# time_circuits1_3.net
KiCad netlist of a schematic drawn in EAGLE
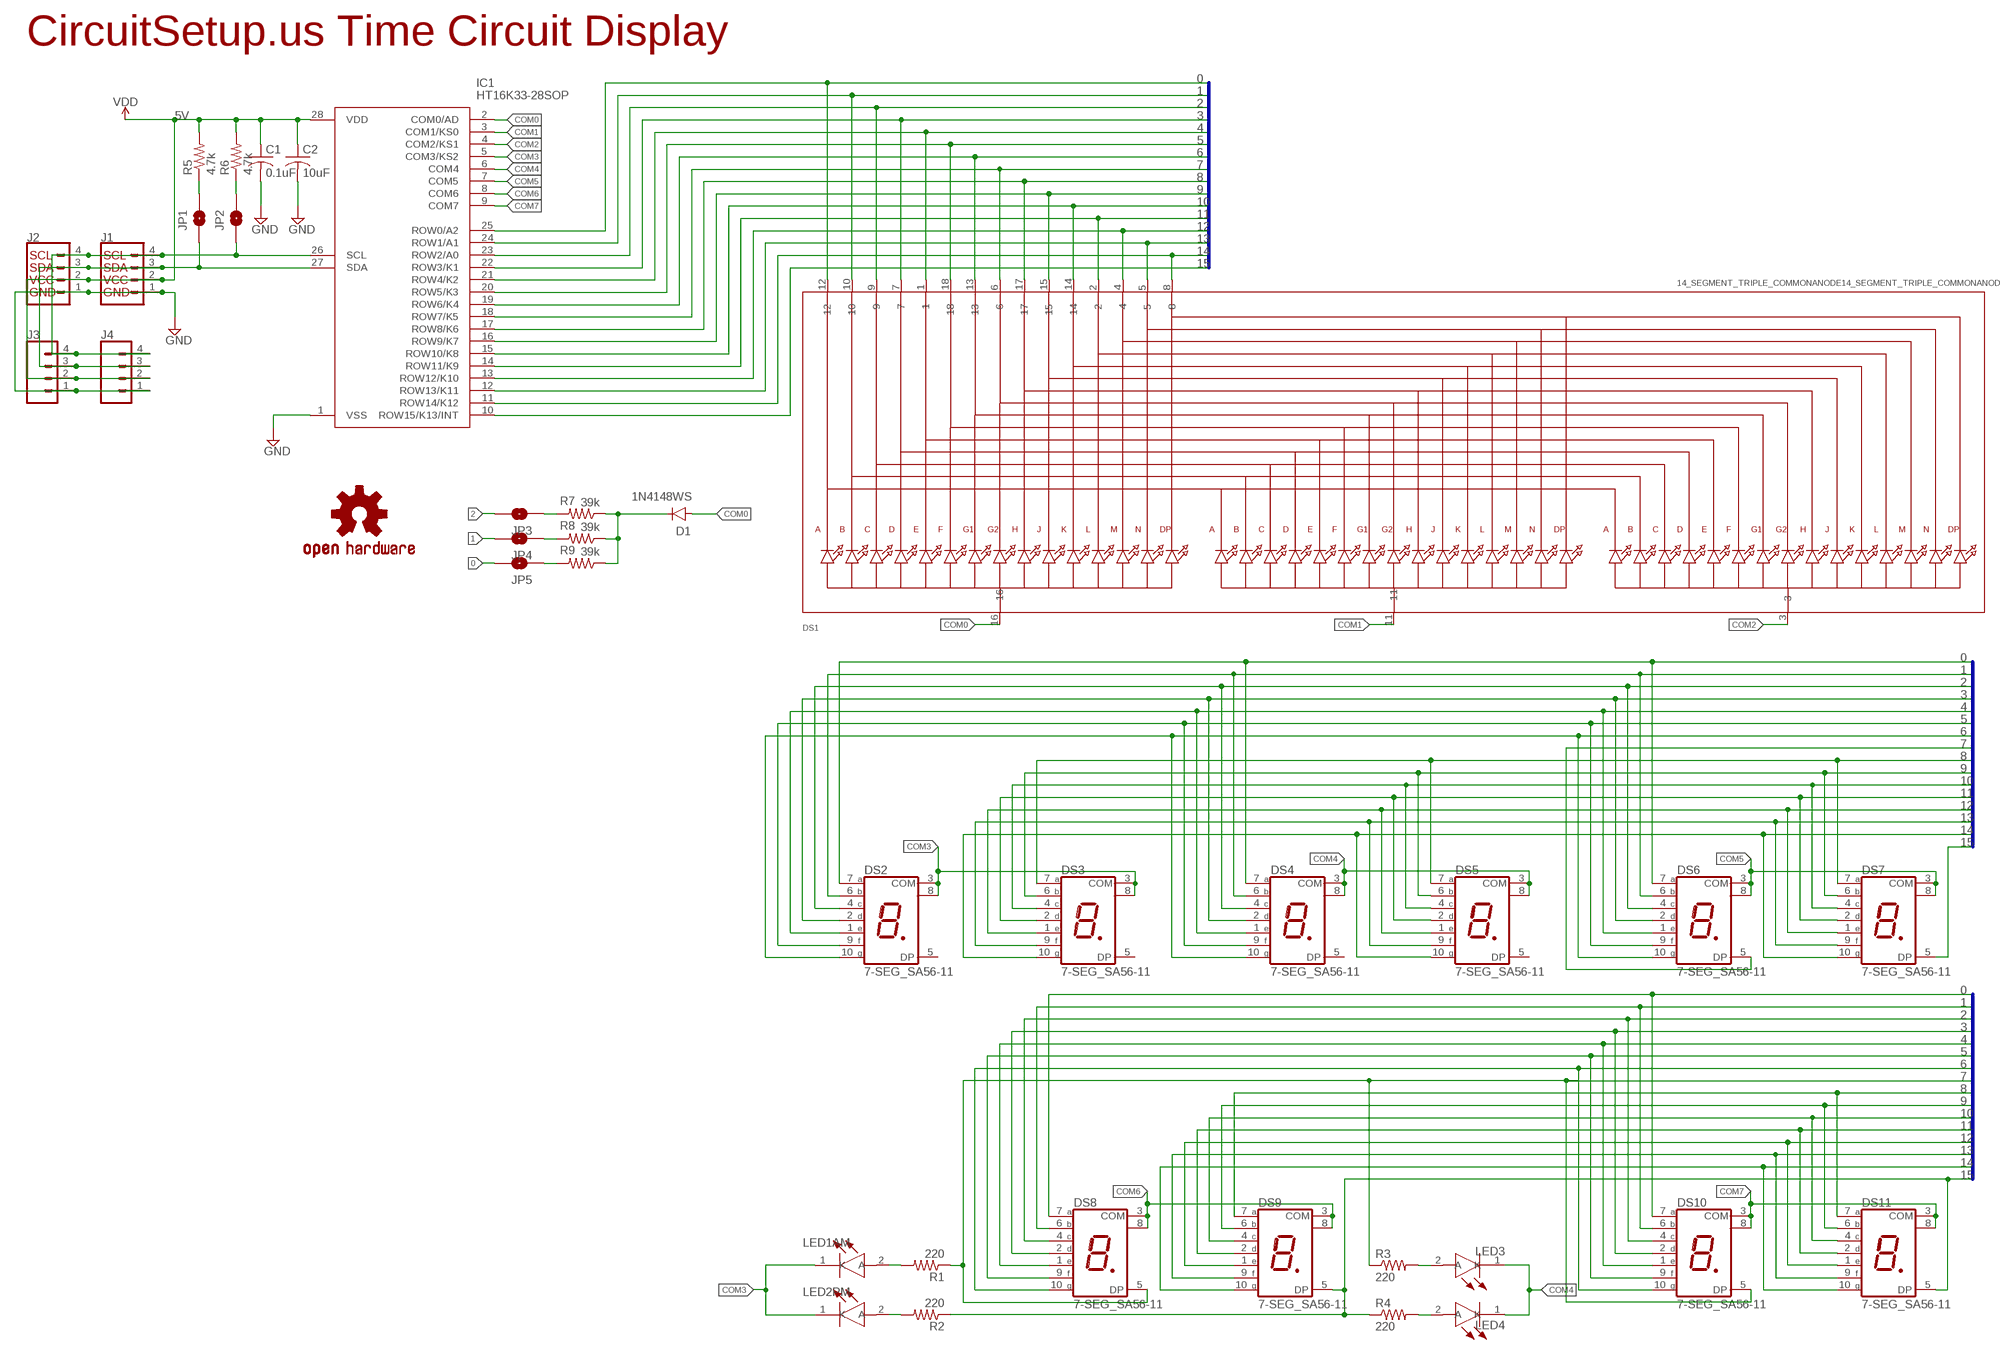
[diagram p0: schematic, sheet 1]

(export (version "E")
  (design (tool "Eeschema 10.0.6"))
  (components
    (comp (ref "C1")
      (value "0.1uF")
      (footprint "eagle-import:C0603")
      (libsource (lib "eagle-import") (part "C-USC0603"))
    )
    (comp (ref "C2")
      (value "10uF")
      (footprint "eagle-import:C0603")
      (libsource (lib "eagle-import") (part "C-USC0603"))
    )
    (comp (ref "D1")
      (value "1N4148WS")
      (footprint "eagle-import:SOD-323")
      (fields
        (field (name "DIGIKEY_PART_NUMBER") "1N4148WSFSTR-ND")
        (field (name "MANUFACTURER") "Diodes Incorporated")
        (field (name "CREATED_BY") "PCBLayout.com")
      )
      (libsource (lib "eagle-import") (part "1N4148WS"))
    )
    (comp (ref "DS1")
      (value "14_SEGMENT_TRIPLE_COMMONANODE14_SEGMENT_TRIPLE_COMMONANODE")
      (footprint "eagle-import:SEGMENT_TRIPLE_14")
      (libsource (lib "eagle-import") (part "14_SEGMENT_TRIPLE_COMMONANODE14_SEGMENT_TRIPLE_COMMONANODE"))
    )
    (comp (ref "DS2")
      (value "7-SEG_SA56-11")
      (footprint "eagle-import:SA56-11")
      (libsource (lib "eagle-import") (part "7-SEG_SA56-11"))
    )
    (comp (ref "DS3")
      (value "7-SEG_SA56-11")
      (footprint "eagle-import:SA56-11")
      (libsource (lib "eagle-import") (part "7-SEG_SA56-11"))
    )
    (comp (ref "DS4")
      (value "7-SEG_SA56-11")
      (footprint "eagle-import:SA56-11")
      (libsource (lib "eagle-import") (part "7-SEG_SA56-11"))
    )
    (comp (ref "DS5")
      (value "7-SEG_SA56-11")
      (footprint "eagle-import:SA56-11")
      (libsource (lib "eagle-import") (part "7-SEG_SA56-11"))
    )
    (comp (ref "DS6")
      (value "7-SEG_SA56-11")
      (footprint "eagle-import:SA56-11")
      (libsource (lib "eagle-import") (part "7-SEG_SA56-11"))
    )
    (comp (ref "DS7")
      (value "7-SEG_SA56-11")
      (footprint "eagle-import:SA56-11")
      (libsource (lib "eagle-import") (part "7-SEG_SA56-11"))
    )
    (comp (ref "DS8")
      (value "7-SEG_SA56-11")
      (footprint "eagle-import:SA56-11")
      (libsource (lib "eagle-import") (part "7-SEG_SA56-11"))
    )
    (comp (ref "DS9")
      (value "7-SEG_SA56-11")
      (footprint "eagle-import:SA56-11")
      (libsource (lib "eagle-import") (part "7-SEG_SA56-11"))
    )
    (comp (ref "DS10")
      (value "7-SEG_SA56-11")
      (footprint "eagle-import:SA56-11")
      (libsource (lib "eagle-import") (part "7-SEG_SA56-11"))
    )
    (comp (ref "DS11")
      (value "7-SEG_SA56-11")
      (footprint "eagle-import:SA56-11")
      (libsource (lib "eagle-import") (part "7-SEG_SA56-11"))
    )
    (comp (ref "IC1")
      (value "HT16K33-28SOP")
      (footprint "eagle-import:SOIC127P1031X264-28N")
      (libsource (lib "eagle-import") (part "HT16K33-28SOP"))
    )
    (comp (ref "J1")
      (value "I2C_STANDARD")
      (footprint "eagle-import:1X04")
      (libsource (lib "eagle-import") (part "I2C_STANDARD"))
    )
    (comp (ref "J2")
      (value "I2C_STANDARD")
      (footprint "eagle-import:1X04")
      (libsource (lib "eagle-import") (part "I2C_STANDARD"))
    )
    (comp (ref "J3")
      (value "CONN_04SMD_2.54")
      (footprint "eagle-import:1X04_5.5MM_STRAIGHT")
      (libsource (lib "eagle-import") (part "CONN_04SMD_2.54"))
    )
    (comp (ref "J4")
      (value "CONN_04SMD_2.54")
      (footprint "eagle-import:1X04_5.5MM_STRAIGHT")
      (libsource (lib "eagle-import") (part "CONN_04SMD_2.54"))
    )
    (comp (ref "JP1")
      (value "JUMPER-SMT_2_NO_SILK")
      (footprint "eagle-import:SMT-JUMPER_2_NO_SILK")
      (libsource (lib "eagle-import") (part "JUMPER-SMT_2_NO_SILK"))
    )
    (comp (ref "JP2")
      (value "JUMPER-SMT_2_NO_SILK")
      (footprint "eagle-import:SMT-JUMPER_2_NO_SILK")
      (libsource (lib "eagle-import") (part "JUMPER-SMT_2_NO_SILK"))
    )
    (comp (ref "JP3")
      (value "JUMPER-SMT_2_NO_SILK")
      (footprint "eagle-import:SMT-JUMPER_2_NO_SILK")
      (libsource (lib "eagle-import") (part "JUMPER-SMT_2_NO_SILK"))
    )
    (comp (ref "JP4")
      (value "JUMPER-SMT_2_NO_SILK")
      (footprint "eagle-import:SMT-JUMPER_2_NO_SILK")
      (libsource (lib "eagle-import") (part "JUMPER-SMT_2_NO_SILK"))
    )
    (comp (ref "JP5")
      (value "JUMPER-SMT_2_NO_SILK")
      (footprint "eagle-import:SMT-JUMPER_2_NO_SILK")
      (libsource (lib "eagle-import") (part "JUMPER-SMT_2_NO_SILK"))
    )
    (comp (ref "LED1AM")
      (value "WP132XGD")
      (footprint "eagle-import:WP132XGD")
      (fields (field (name "MOUSER_PART_NUMBER") "604-WP132XGD"))
      (libsource (lib "eagle-import") (part "WP132XGD"))
    )
    (comp (ref "LED2PM")
      (value "WP132XGD")
      (footprint "eagle-import:WP132XGD")
      (fields (field (name "MOUSER_PART_NUMBER") "604-WP132XGD"))
      (libsource (lib "eagle-import") (part "WP132XGD"))
    )
    (comp (ref "LED3")
      (value "WP132XGD")
      (footprint "eagle-import:WP132XGD")
      (fields (field (name "MOUSER_PART_NUMBER") "604-WP132XGD"))
      (libsource (lib "eagle-import") (part "WP132XGD"))
    )
    (comp (ref "LED4")
      (value "WP132XGD")
      (footprint "eagle-import:WP132XGD")
      (fields (field (name "MOUSER_PART_NUMBER") "604-WP132XGD"))
      (libsource (lib "eagle-import") (part "WP132XGD"))
    )
    (comp (ref "LOGO1")
      (value "OSHW-LOGOL")
      (footprint "eagle-import:OSHW-LOGO-L")
      (libsource (lib "eagle-import") (part "OSHW-LOGOL"))
    )
    (comp (ref "R1")
      (value "220")
      (footprint "eagle-import:R0603")
      (libsource (lib "eagle-import") (part "R-US_R0603"))
    )
    (comp (ref "R2")
      (value "220")
      (footprint "eagle-import:R0603")
      (libsource (lib "eagle-import") (part "R-US_R0603"))
    )
    (comp (ref "R3")
      (value "220")
      (footprint "eagle-import:R0603")
      (libsource (lib "eagle-import") (part "R-US_R0603"))
    )
    (comp (ref "R4")
      (value "220")
      (footprint "eagle-import:R0603")
      (libsource (lib "eagle-import") (part "R-US_R0603"))
    )
    (comp (ref "R5")
      (value "4.7k")
      (footprint "eagle-import:R0603")
      (libsource (lib "eagle-import") (part "R-US_R0603"))
    )
    (comp (ref "R6")
      (value "4.7k")
      (footprint "eagle-import:R0603")
      (libsource (lib "eagle-import") (part "R-US_R0603"))
    )
    (comp (ref "R7")
      (value "39k")
      (footprint "eagle-import:R0603")
      (libsource (lib "eagle-import") (part "R-US_R0603"))
    )
    (comp (ref "R8")
      (value "39k")
      (footprint "eagle-import:R0603")
      (libsource (lib "eagle-import") (part "R-US_R0603"))
    )
    (comp (ref "R9")
      (value "39k")
      (footprint "eagle-import:R0603")
      (libsource (lib "eagle-import") (part "R-US_R0603"))
    )
  )
  (nets
    (net (code "1") (name "/3") (class "Default")
      (node (ref "DS1") (pin "7") (pinfunction "7_7") (pintype "bidirectional"))
      (node (ref "DS10") (pin "2") (pinfunction "D_2") (pintype "passive"))
      (node (ref "DS2") (pin "2") (pinfunction "D_2") (pintype "passive"))
      (node (ref "DS4") (pin "2") (pinfunction "D_2") (pintype "passive"))
      (node (ref "DS6") (pin "2") (pinfunction "D_2") (pintype "passive"))
      (node (ref "DS8") (pin "2") (pinfunction "D_2") (pintype "passive"))
      (node (ref "IC1") (pin "22") (pinfunction "ROW3/K1_22") (pintype "bidirectional"))
    )
    (net (code "2") (name "/4") (class "Default")
      (node (ref "DS1") (pin "1") (pinfunction "1_1") (pintype "bidirectional"))
      (node (ref "DS10") (pin "1") (pinfunction "E_1") (pintype "passive"))
      (node (ref "DS2") (pin "1") (pinfunction "E_1") (pintype "passive"))
      (node (ref "DS4") (pin "1") (pinfunction "E_1") (pintype "passive"))
      (node (ref "DS6") (pin "1") (pinfunction "E_1") (pintype "passive"))
      (node (ref "DS8") (pin "1") (pinfunction "E_1") (pintype "passive"))
      (node (ref "IC1") (pin "21") (pinfunction "ROW4/K2_21") (pintype "bidirectional"))
    )
    (net (code "3") (name "/5") (class "Default")
      (node (ref "DS1") (pin "18") (pinfunction "18_18") (pintype "bidirectional"))
      (node (ref "DS10") (pin "9") (pinfunction "F_9") (pintype "passive"))
      (node (ref "DS2") (pin "9") (pinfunction "F_9") (pintype "passive"))
      (node (ref "DS4") (pin "9") (pinfunction "F_9") (pintype "passive"))
      (node (ref "DS6") (pin "9") (pinfunction "F_9") (pintype "passive"))
      (node (ref "DS8") (pin "9") (pinfunction "F_9") (pintype "passive"))
      (node (ref "IC1") (pin "20") (pinfunction "ROW5/K3_20") (pintype "bidirectional"))
    )
    (net (code "4") (name "/6") (class "Default")
      (node (ref "DS1") (pin "13") (pinfunction "13_13") (pintype "bidirectional"))
      (node (ref "DS10") (pin "10") (pinfunction "G_10") (pintype "passive"))
      (node (ref "DS2") (pin "10") (pinfunction "G_10") (pintype "passive"))
      (node (ref "DS4") (pin "10") (pinfunction "G_10") (pintype "passive"))
      (node (ref "DS6") (pin "10") (pinfunction "G_10") (pintype "passive"))
      (node (ref "DS8") (pin "10") (pinfunction "G_10") (pintype "passive"))
      (node (ref "IC1") (pin "19") (pinfunction "ROW6/K4_19") (pintype "bidirectional"))
    )
    (net (code "5") (name "/7") (class "Default")
      (node (ref "DS1") (pin "6") (pinfunction "6_6") (pintype "bidirectional"))
      (node (ref "DS10") (pin "5") (pinfunction "DP_5") (pintype "passive"))
      (node (ref "DS6") (pin "5") (pinfunction "DP_5") (pintype "passive"))
      (node (ref "DS8") (pin "5") (pinfunction "DP_5") (pintype "passive"))
      (node (ref "IC1") (pin "18") (pinfunction "ROW7/K5_18") (pintype "bidirectional"))
      (node (ref "R1") (pin "1") (pinfunction "1_1") (pintype "passive"))
      (node (ref "R3") (pin "1") (pinfunction "1_1") (pintype "passive"))
    )
    (net (code "6") (name "/8") (class "Default")
      (node (ref "DS1") (pin "17") (pinfunction "17_17") (pintype "bidirectional"))
      (node (ref "DS11") (pin "7") (pinfunction "A_7") (pintype "passive"))
      (node (ref "DS3") (pin "7") (pinfunction "A_7") (pintype "passive"))
      (node (ref "DS5") (pin "7") (pinfunction "A_7") (pintype "passive"))
      (node (ref "DS7") (pin "7") (pinfunction "A_7") (pintype "passive"))
      (node (ref "DS9") (pin "7") (pinfunction "A_7") (pintype "passive"))
      (node (ref "IC1") (pin "17") (pinfunction "ROW8/K6_17") (pintype "bidirectional"))
    )
    (net (code "7") (name "/9") (class "Default")
      (node (ref "DS1") (pin "15") (pinfunction "15_15") (pintype "bidirectional"))
      (node (ref "DS11") (pin "6") (pinfunction "B_6") (pintype "passive"))
      (node (ref "DS3") (pin "6") (pinfunction "B_6") (pintype "passive"))
      (node (ref "DS5") (pin "6") (pinfunction "B_6") (pintype "passive"))
      (node (ref "DS7") (pin "6") (pinfunction "B_6") (pintype "passive"))
      (node (ref "DS9") (pin "6") (pinfunction "B_6") (pintype "passive"))
      (node (ref "IC1") (pin "16") (pinfunction "ROW9/K7_16") (pintype "bidirectional"))
    )
    (net (code "8") (name "/10") (class "Default")
      (node (ref "DS1") (pin "14") (pinfunction "14_14") (pintype "bidirectional"))
      (node (ref "DS11") (pin "4") (pinfunction "C_4") (pintype "passive"))
      (node (ref "DS3") (pin "4") (pinfunction "C_4") (pintype "passive"))
      (node (ref "DS5") (pin "4") (pinfunction "C_4") (pintype "passive"))
      (node (ref "DS7") (pin "4") (pinfunction "C_4") (pintype "passive"))
      (node (ref "DS9") (pin "4") (pinfunction "C_4") (pintype "passive"))
      (node (ref "IC1") (pin "15") (pinfunction "ROW10/K8_15") (pintype "bidirectional"))
    )
    (net (code "9") (name "/11") (class "Default")
      (node (ref "DS1") (pin "2") (pinfunction "2_2") (pintype "bidirectional"))
      (node (ref "DS11") (pin "2") (pinfunction "D_2") (pintype "passive"))
      (node (ref "DS3") (pin "2") (pinfunction "D_2") (pintype "passive"))
      (node (ref "DS5") (pin "2") (pinfunction "D_2") (pintype "passive"))
      (node (ref "DS7") (pin "2") (pinfunction "D_2") (pintype "passive"))
      (node (ref "DS9") (pin "2") (pinfunction "D_2") (pintype "passive"))
      (node (ref "IC1") (pin "14") (pinfunction "ROW11/K9_14") (pintype "bidirectional"))
    )
    (net (code "10") (name "/12") (class "Default")
      (node (ref "DS1") (pin "4") (pinfunction "4_4") (pintype "bidirectional"))
      (node (ref "DS11") (pin "1") (pinfunction "E_1") (pintype "passive"))
      (node (ref "DS3") (pin "1") (pinfunction "E_1") (pintype "passive"))
      (node (ref "DS5") (pin "1") (pinfunction "E_1") (pintype "passive"))
      (node (ref "DS7") (pin "1") (pinfunction "E_1") (pintype "passive"))
      (node (ref "DS9") (pin "1") (pinfunction "E_1") (pintype "passive"))
      (node (ref "IC1") (pin "13") (pinfunction "ROW12/K10_13") (pintype "bidirectional"))
    )
    (net (code "11") (name "/13") (class "Default")
      (node (ref "DS1") (pin "5") (pinfunction "5_5") (pintype "bidirectional"))
      (node (ref "DS11") (pin "9") (pinfunction "F_9") (pintype "passive"))
      (node (ref "DS3") (pin "9") (pinfunction "F_9") (pintype "passive"))
      (node (ref "DS5") (pin "9") (pinfunction "F_9") (pintype "passive"))
      (node (ref "DS7") (pin "9") (pinfunction "F_9") (pintype "passive"))
      (node (ref "DS9") (pin "9") (pinfunction "F_9") (pintype "passive"))
      (node (ref "IC1") (pin "12") (pinfunction "ROW13/K11_12") (pintype "bidirectional"))
    )
    (net (code "12") (name "/14") (class "Default")
      (node (ref "DS1") (pin "8") (pinfunction "8_8") (pintype "bidirectional"))
      (node (ref "DS11") (pin "10") (pinfunction "G_10") (pintype "passive"))
      (node (ref "DS3") (pin "10") (pinfunction "G_10") (pintype "passive"))
      (node (ref "DS5") (pin "10") (pinfunction "G_10") (pintype "passive"))
      (node (ref "DS7") (pin "10") (pinfunction "G_10") (pintype "passive"))
      (node (ref "DS9") (pin "10") (pinfunction "G_10") (pintype "passive"))
      (node (ref "IC1") (pin "11") (pinfunction "ROW14/K12_11") (pintype "bidirectional"))
    )
    (net (code "13") (name "/15") (class "Default")
      (node (ref "DS11") (pin "5") (pinfunction "DP_5") (pintype "passive"))
      (node (ref "DS7") (pin "5") (pinfunction "DP_5") (pintype "passive"))
      (node (ref "DS9") (pin "5") (pinfunction "DP_5") (pintype "passive"))
      (node (ref "IC1") (pin "10") (pinfunction "ROW15/K13/INT_10") (pintype "bidirectional"))
      (node (ref "R2") (pin "1") (pinfunction "1_1") (pintype "passive"))
      (node (ref "R4") (pin "1") (pinfunction "1_1") (pintype "passive"))
    )
    (net (code "14") (name "0") (class "Default")
      (node (ref "DS1") (pin "12") (pinfunction "12_12") (pintype "bidirectional"))
      (node (ref "DS10") (pin "7") (pinfunction "A_7") (pintype "passive"))
      (node (ref "DS2") (pin "7") (pinfunction "A_7") (pintype "passive"))
      (node (ref "DS4") (pin "7") (pinfunction "A_7") (pintype "passive"))
      (node (ref "DS6") (pin "7") (pinfunction "A_7") (pintype "passive"))
      (node (ref "DS8") (pin "7") (pinfunction "A_7") (pintype "passive"))
      (node (ref "IC1") (pin "25") (pinfunction "ROW0/A2_25") (pintype "bidirectional"))
      (node (ref "JP5") (pin "2") (pinfunction "2_2") (pintype "passive"))
    )
    (net (code "15") (name "1") (class "Default")
      (node (ref "DS1") (pin "10") (pinfunction "10_10") (pintype "bidirectional"))
      (node (ref "DS10") (pin "6") (pinfunction "B_6") (pintype "passive"))
      (node (ref "DS2") (pin "6") (pinfunction "B_6") (pintype "passive"))
      (node (ref "DS4") (pin "6") (pinfunction "B_6") (pintype "passive"))
      (node (ref "DS6") (pin "6") (pinfunction "B_6") (pintype "passive"))
      (node (ref "DS8") (pin "6") (pinfunction "B_6") (pintype "passive"))
      (node (ref "IC1") (pin "24") (pinfunction "ROW1/A1_24") (pintype "bidirectional"))
      (node (ref "JP4") (pin "2") (pinfunction "2_2") (pintype "passive"))
    )
    (net (code "16") (name "2") (class "Default")
      (node (ref "DS1") (pin "9") (pinfunction "9_9") (pintype "bidirectional"))
      (node (ref "DS10") (pin "4") (pinfunction "C_4") (pintype "passive"))
      (node (ref "DS2") (pin "4") (pinfunction "C_4") (pintype "passive"))
      (node (ref "DS4") (pin "4") (pinfunction "C_4") (pintype "passive"))
      (node (ref "DS6") (pin "4") (pinfunction "C_4") (pintype "passive"))
      (node (ref "DS8") (pin "4") (pinfunction "C_4") (pintype "passive"))
      (node (ref "IC1") (pin "23") (pinfunction "ROW2/A0_23") (pintype "bidirectional"))
      (node (ref "JP3") (pin "2") (pinfunction "2_2") (pintype "passive"))
    )
    (net (code "17") (name "COM0") (class "Default")
      (node (ref "D1") (pin "A") (pinfunction "A_A") (pintype "passive"))
      (node (ref "DS1") (pin "16") (pinfunction "16_16") (pintype "bidirectional"))
      (node (ref "IC1") (pin "2") (pinfunction "COM0/AD_2") (pintype "bidirectional"))
    )
    (net (code "18") (name "COM1") (class "Default")
      (node (ref "DS1") (pin "11") (pinfunction "11_11") (pintype "bidirectional"))
      (node (ref "IC1") (pin "3") (pinfunction "COM1/KS0_3") (pintype "bidirectional"))
    )
    (net (code "19") (name "COM2") (class "Default")
      (node (ref "DS1") (pin "3") (pinfunction "3_3") (pintype "bidirectional"))
      (node (ref "IC1") (pin "4") (pinfunction "COM2/KS1_4") (pintype "bidirectional"))
    )
    (net (code "20") (name "COM3") (class "Default")
      (node (ref "DS2") (pin "3") (pinfunction "COM_3") (pintype "passive"))
      (node (ref "DS2") (pin "8") (pinfunction "COM_8") (pintype "passive"))
      (node (ref "DS3") (pin "3") (pinfunction "COM_3") (pintype "passive"))
      (node (ref "DS3") (pin "8") (pinfunction "COM_8") (pintype "passive"))
      (node (ref "IC1") (pin "5") (pinfunction "COM3/KS2_5") (pintype "bidirectional"))
      (node (ref "LED1AM") (pin "1") (pinfunction "K_1") (pintype "bidirectional"))
      (node (ref "LED2PM") (pin "1") (pinfunction "K_1") (pintype "bidirectional"))
    )
    (net (code "21") (name "COM4") (class "Default")
      (node (ref "DS4") (pin "3") (pinfunction "COM_3") (pintype "passive"))
      (node (ref "DS4") (pin "8") (pinfunction "COM_8") (pintype "passive"))
      (node (ref "DS5") (pin "3") (pinfunction "COM_3") (pintype "passive"))
      (node (ref "DS5") (pin "8") (pinfunction "COM_8") (pintype "passive"))
      (node (ref "IC1") (pin "6") (pinfunction "COM4_6") (pintype "bidirectional"))
      (node (ref "LED3") (pin "1") (pinfunction "K_1") (pintype "bidirectional"))
      (node (ref "LED4") (pin "1") (pinfunction "K_1") (pintype "bidirectional"))
    )
    (net (code "22") (name "COM5") (class "Default")
      (node (ref "DS6") (pin "3") (pinfunction "COM_3") (pintype "passive"))
      (node (ref "DS6") (pin "8") (pinfunction "COM_8") (pintype "passive"))
      (node (ref "DS7") (pin "3") (pinfunction "COM_3") (pintype "passive"))
      (node (ref "DS7") (pin "8") (pinfunction "COM_8") (pintype "passive"))
      (node (ref "IC1") (pin "7") (pinfunction "COM5_7") (pintype "bidirectional"))
    )
    (net (code "23") (name "COM6") (class "Default")
      (node (ref "DS8") (pin "3") (pinfunction "COM_3") (pintype "passive"))
      (node (ref "DS8") (pin "8") (pinfunction "COM_8") (pintype "passive"))
      (node (ref "DS9") (pin "3") (pinfunction "COM_3") (pintype "passive"))
      (node (ref "DS9") (pin "8") (pinfunction "COM_8") (pintype "passive"))
      (node (ref "IC1") (pin "8") (pinfunction "COM6_8") (pintype "bidirectional"))
    )
    (net (code "24") (name "COM7") (class "Default")
      (node (ref "DS10") (pin "3") (pinfunction "COM_3") (pintype "passive"))
      (node (ref "DS10") (pin "8") (pinfunction "COM_8") (pintype "passive"))
      (node (ref "DS11") (pin "3") (pinfunction "COM_3") (pintype "passive"))
      (node (ref "DS11") (pin "8") (pinfunction "COM_8") (pintype "passive"))
      (node (ref "IC1") (pin "9") (pinfunction "COM7_9") (pintype "bidirectional"))
    )
    (net (code "25") (name "GND") (class "Default")
      (node (ref "C1") (pin "2") (pinfunction "2_2") (pintype "passive"))
      (node (ref "C2") (pin "2") (pinfunction "2_2") (pintype "passive"))
      (node (ref "IC1") (pin "1") (pinfunction "VSS_1") (pintype "bidirectional"))
      (node (ref "J1") (pin "1") (pinfunction "1_1") (pintype "power_in"))
      (node (ref "J2") (pin "1") (pinfunction "1_1") (pintype "power_in"))
      (node (ref "J3") (pin "1") (pinfunction "1_1") (pintype "passive"))
      (node (ref "J4") (pin "1") (pinfunction "1_1") (pintype "passive"))
    )
    (net (code "26") (name "Net-(D1-PadC)") (class "Default")
      (node (ref "D1") (pin "C") (pinfunction "C_C") (pintype "passive"))
      (node (ref "R7") (pin "1") (pinfunction "1_1") (pintype "passive"))
      (node (ref "R8") (pin "1") (pinfunction "1_1") (pintype "passive"))
      (node (ref "R9") (pin "1") (pinfunction "1_1") (pintype "passive"))
    )
    (net (code "27") (name "Net-(IC1-SCL)") (class "Default")
      (node (ref "IC1") (pin "26") (pinfunction "SCL_26") (pintype "bidirectional"))
      (node (ref "J1") (pin "4") (pinfunction "4_4") (pintype "passive"))
      (node (ref "J2") (pin "4") (pinfunction "4_4") (pintype "passive"))
      (node (ref "J3") (pin "4") (pinfunction "4_4") (pintype "passive"))
      (node (ref "J4") (pin "4") (pinfunction "4_4") (pintype "passive"))
      (node (ref "JP2") (pin "1") (pinfunction "1_1") (pintype "passive"))
    )
    (net (code "28") (name "Net-(IC1-SDA)") (class "Default")
      (node (ref "IC1") (pin "27") (pinfunction "SDA_27") (pintype "bidirectional"))
      (node (ref "J1") (pin "3") (pinfunction "3_3") (pintype "passive"))
      (node (ref "J2") (pin "3") (pinfunction "3_3") (pintype "passive"))
      (node (ref "J3") (pin "3") (pinfunction "3_3") (pintype "passive"))
      (node (ref "J4") (pin "3") (pinfunction "3_3") (pintype "passive"))
      (node (ref "JP1") (pin "1") (pinfunction "1_1") (pintype "passive"))
    )
    (net (code "29") (name "Net-(JP1-Pad2)") (class "Default")
      (node (ref "JP1") (pin "2") (pinfunction "2_2") (pintype "passive"))
      (node (ref "R5") (pin "1") (pinfunction "1_1") (pintype "passive"))
    )
    (net (code "30") (name "Net-(JP2-Pad2)") (class "Default")
      (node (ref "JP2") (pin "2") (pinfunction "2_2") (pintype "passive"))
      (node (ref "R6") (pin "1") (pinfunction "1_1") (pintype "passive"))
    )
    (net (code "31") (name "Net-(JP3-Pad1)") (class "Default")
      (node (ref "JP3") (pin "1") (pinfunction "1_1") (pintype "passive"))
      (node (ref "R7") (pin "2") (pinfunction "2_2") (pintype "passive"))
    )
    (net (code "32") (name "Net-(JP4-Pad1)") (class "Default")
      (node (ref "JP4") (pin "1") (pinfunction "1_1") (pintype "passive"))
      (node (ref "R8") (pin "2") (pinfunction "2_2") (pintype "passive"))
    )
    (net (code "33") (name "Net-(JP5-Pad1)") (class "Default")
      (node (ref "JP5") (pin "1") (pinfunction "1_1") (pintype "passive"))
      (node (ref "R9") (pin "2") (pinfunction "2_2") (pintype "passive"))
    )
    (net (code "34") (name "Net-(LED1AM-A)") (class "Default")
      (node (ref "LED1AM") (pin "2") (pinfunction "A_2") (pintype "bidirectional"))
      (node (ref "R1") (pin "2") (pinfunction "2_2") (pintype "passive"))
    )
    (net (code "35") (name "Net-(LED2PM-A)") (class "Default")
      (node (ref "LED2PM") (pin "2") (pinfunction "A_2") (pintype "bidirectional"))
      (node (ref "R2") (pin "2") (pinfunction "2_2") (pintype "passive"))
    )
    (net (code "36") (name "Net-(LED3-A)") (class "Default")
      (node (ref "LED3") (pin "2") (pinfunction "A_2") (pintype "bidirectional"))
      (node (ref "R3") (pin "2") (pinfunction "2_2") (pintype "passive"))
    )
    (net (code "37") (name "Net-(LED4-A)") (class "Default")
      (node (ref "LED4") (pin "2") (pinfunction "A_2") (pintype "bidirectional"))
      (node (ref "R4") (pin "2") (pinfunction "2_2") (pintype "passive"))
    )
    (net (code "38") (name "VDD") (class "Default")
      (node (ref "C1") (pin "1") (pinfunction "1_1") (pintype "passive"))
      (node (ref "C2") (pin "1") (pinfunction "1_1") (pintype "passive"))
      (node (ref "IC1") (pin "28") (pinfunction "VDD_28") (pintype "bidirectional"))
      (node (ref "J1") (pin "2") (pinfunction "2_2") (pintype "power_in"))
      (node (ref "J2") (pin "2") (pinfunction "2_2") (pintype "power_in"))
      (node (ref "J3") (pin "2") (pinfunction "2_2") (pintype "passive"))
      (node (ref "J4") (pin "2") (pinfunction "2_2") (pintype "passive"))
      (node (ref "R5") (pin "2") (pinfunction "2_2") (pintype "passive"))
      (node (ref "R6") (pin "2") (pinfunction "2_2") (pintype "passive"))
    )
    (net (code "39") (name "unconnected-(DS2-DP-Pad5)") (class "Default")
      (node (ref "DS2") (pin "5") (pinfunction "DP_5") (pintype "passive"))
    )
    (net (code "40") (name "unconnected-(DS3-DP-Pad5)") (class "Default")
      (node (ref "DS3") (pin "5") (pinfunction "DP_5") (pintype "passive"))
    )
    (net (code "41") (name "unconnected-(DS4-DP-Pad5)") (class "Default")
      (node (ref "DS4") (pin "5") (pinfunction "DP_5") (pintype "passive"))
    )
    (net (code "42") (name "unconnected-(DS5-DP-Pad5)") (class "Default")
      (node (ref "DS5") (pin "5") (pinfunction "DP_5") (pintype "passive"))
    )
  )
)
